# charlie_array_0805_v1.net
KiCad netlist of a schematic drawn in EAGLE
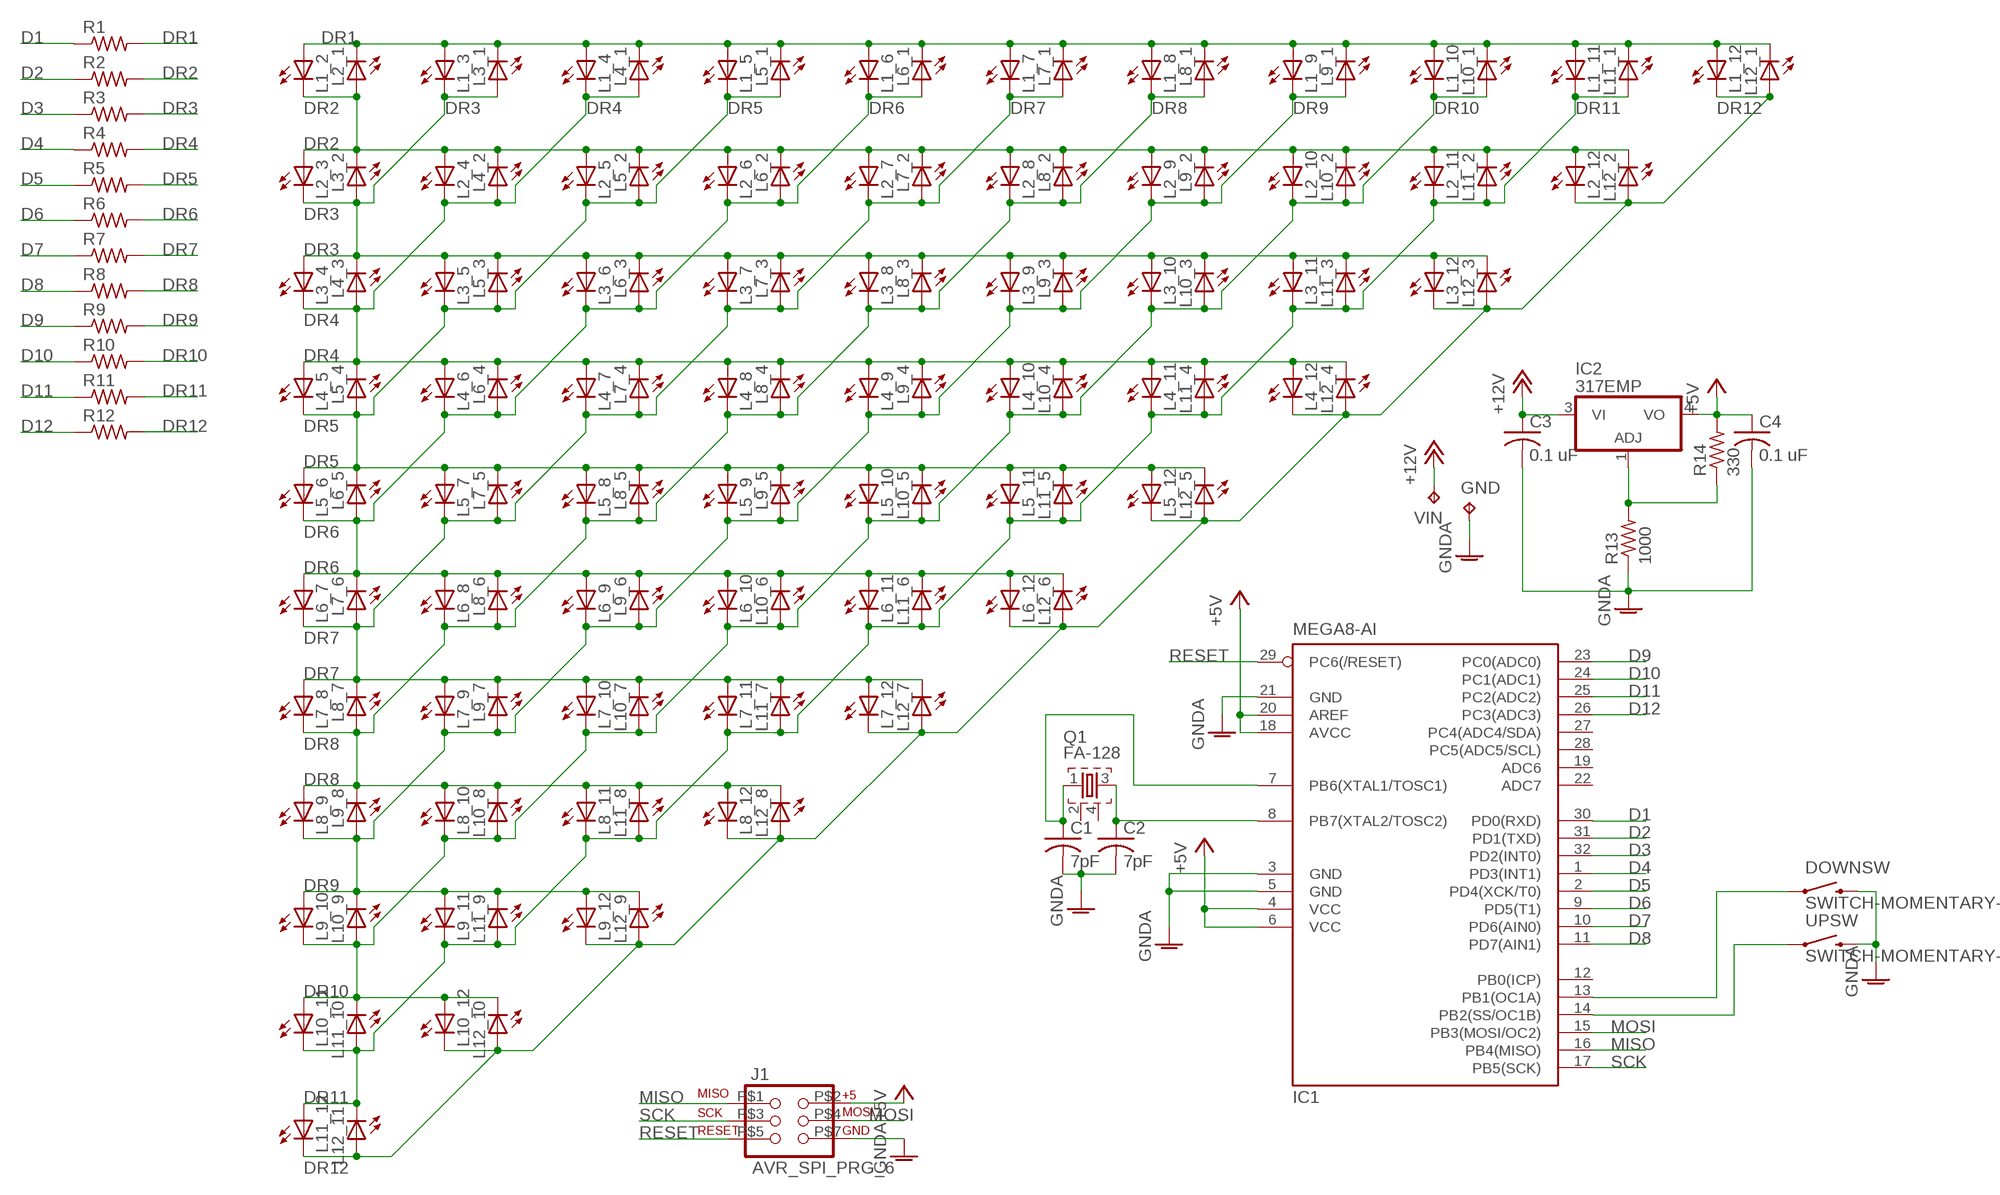
[diagram p0: schematic, sheet 1]

(export (version "E")
  (design (tool "Eeschema 10.0.6"))
  (components
    (comp (ref "C1")
      (value "7pF")
      (footprint "eagle-import:C0603")
      (libsource (lib "eagle-import") (part "C-USC0603"))
    )
    (comp (ref "C2")
      (value "7pF")
      (footprint "eagle-import:C0603")
      (libsource (lib "eagle-import") (part "C-USC0603"))
    )
    (comp (ref "C3")
      (value "0.1 uF")
      (footprint "eagle-import:C0603")
      (libsource (lib "eagle-import") (part "C-USC0603"))
    )
    (comp (ref "C4")
      (value "0.1 uF")
      (footprint "eagle-import:C0603")
      (libsource (lib "eagle-import") (part "C-USC0603"))
    )
    (comp (ref "DOWNSW")
      (value "SWITCH-MOMENTARY-2")
      (footprint "eagle-import:TACTILE_SWITCH_TALL")
      (libsource (lib "eagle-import") (part "SWITCH-MOMENTARY-2"))
    )
    (comp (ref "GND")
      (value "TPTP20SQ")
      (footprint "eagle-import:TP20SQ")
      (libsource (lib "eagle-import") (part "TPTP20SQ"))
    )
    (comp (ref "IC1")
      (value "MEGA8-AI")
      (footprint "eagle-import:TQFP32-08")
      (fields (field (name "MPN") "ATMEGA8-16AU"))
      (libsource (lib "eagle-import") (part "MEGA8-AI"))
    )
    (comp (ref "IC2")
      (value "317EMP")
      (footprint "eagle-import:SOT223")
      (libsource (lib "eagle-import") (part "317EMP"))
    )
    (comp (ref "J1")
      (value "AVR_SPI_PRG_6")
      (footprint "eagle-import:2X3_ICSP_SMD")
      (libsource (lib "eagle-import") (part "AVR_SPI_PRG_6"))
    )
    (comp (ref "L1_2")
      (value "LEDCHIPLED_0805")
      (footprint "eagle-import:CHIPLED_0805")
      (libsource (lib "eagle-import") (part "LEDCHIPLED_0805"))
    )
    (comp (ref "L1_3")
      (value "LEDCHIPLED_0805")
      (footprint "eagle-import:CHIPLED_0805")
      (libsource (lib "eagle-import") (part "LEDCHIPLED_0805"))
    )
    (comp (ref "L1_4")
      (value "LEDCHIPLED_0805")
      (footprint "eagle-import:CHIPLED_0805")
      (libsource (lib "eagle-import") (part "LEDCHIPLED_0805"))
    )
    (comp (ref "L1_5")
      (value "LEDCHIPLED_0805")
      (footprint "eagle-import:CHIPLED_0805")
      (libsource (lib "eagle-import") (part "LEDCHIPLED_0805"))
    )
    (comp (ref "L1_6")
      (value "LEDCHIPLED_0805")
      (footprint "eagle-import:CHIPLED_0805")
      (libsource (lib "eagle-import") (part "LEDCHIPLED_0805"))
    )
    (comp (ref "L1_7")
      (value "LEDCHIPLED_0805")
      (footprint "eagle-import:CHIPLED_0805")
      (libsource (lib "eagle-import") (part "LEDCHIPLED_0805"))
    )
    (comp (ref "L1_8")
      (value "LEDCHIPLED_0805")
      (footprint "eagle-import:CHIPLED_0805")
      (libsource (lib "eagle-import") (part "LEDCHIPLED_0805"))
    )
    (comp (ref "L1_9")
      (value "LEDCHIPLED_0805")
      (footprint "eagle-import:CHIPLED_0805")
      (libsource (lib "eagle-import") (part "LEDCHIPLED_0805"))
    )
    (comp (ref "L1_10")
      (value "LEDCHIPLED_0805")
      (footprint "eagle-import:CHIPLED_0805")
      (libsource (lib "eagle-import") (part "LEDCHIPLED_0805"))
    )
    (comp (ref "L1_11")
      (value "LEDCHIPLED_0805")
      (footprint "eagle-import:CHIPLED_0805")
      (libsource (lib "eagle-import") (part "LEDCHIPLED_0805"))
    )
    (comp (ref "L1_12")
      (value "LEDCHIPLED_0805")
      (footprint "eagle-import:CHIPLED_0805")
      (libsource (lib "eagle-import") (part "LEDCHIPLED_0805"))
    )
    (comp (ref "L2_1")
      (value "LEDCHIPLED_0805")
      (footprint "eagle-import:CHIPLED_0805")
      (libsource (lib "eagle-import") (part "LEDCHIPLED_0805"))
    )
    (comp (ref "L2_3")
      (value "LEDCHIPLED_0805")
      (footprint "eagle-import:CHIPLED_0805")
      (libsource (lib "eagle-import") (part "LEDCHIPLED_0805"))
    )
    (comp (ref "L2_4")
      (value "LEDCHIPLED_0805")
      (footprint "eagle-import:CHIPLED_0805")
      (libsource (lib "eagle-import") (part "LEDCHIPLED_0805"))
    )
    (comp (ref "L2_5")
      (value "LEDCHIPLED_0805")
      (footprint "eagle-import:CHIPLED_0805")
      (libsource (lib "eagle-import") (part "LEDCHIPLED_0805"))
    )
    (comp (ref "L2_6")
      (value "LEDCHIPLED_0805")
      (footprint "eagle-import:CHIPLED_0805")
      (libsource (lib "eagle-import") (part "LEDCHIPLED_0805"))
    )
    (comp (ref "L2_7")
      (value "LEDCHIPLED_0805")
      (footprint "eagle-import:CHIPLED_0805")
      (libsource (lib "eagle-import") (part "LEDCHIPLED_0805"))
    )
    (comp (ref "L2_8")
      (value "LEDCHIPLED_0805")
      (footprint "eagle-import:CHIPLED_0805")
      (libsource (lib "eagle-import") (part "LEDCHIPLED_0805"))
    )
    (comp (ref "L2_9")
      (value "LEDCHIPLED_0805")
      (footprint "eagle-import:CHIPLED_0805")
      (libsource (lib "eagle-import") (part "LEDCHIPLED_0805"))
    )
    (comp (ref "L2_10")
      (value "LEDCHIPLED_0805")
      (footprint "eagle-import:CHIPLED_0805")
      (libsource (lib "eagle-import") (part "LEDCHIPLED_0805"))
    )
    (comp (ref "L2_11")
      (value "LEDCHIPLED_0805")
      (footprint "eagle-import:CHIPLED_0805")
      (libsource (lib "eagle-import") (part "LEDCHIPLED_0805"))
    )
    (comp (ref "L2_12")
      (value "LEDCHIPLED_0805")
      (footprint "eagle-import:CHIPLED_0805")
      (libsource (lib "eagle-import") (part "LEDCHIPLED_0805"))
    )
    (comp (ref "L3_1")
      (value "LEDCHIPLED_0805")
      (footprint "eagle-import:CHIPLED_0805")
      (libsource (lib "eagle-import") (part "LEDCHIPLED_0805"))
    )
    (comp (ref "L3_2")
      (value "LEDCHIPLED_0805")
      (footprint "eagle-import:CHIPLED_0805")
      (libsource (lib "eagle-import") (part "LEDCHIPLED_0805"))
    )
    (comp (ref "L3_4")
      (value "LEDCHIPLED_0805")
      (footprint "eagle-import:CHIPLED_0805")
      (libsource (lib "eagle-import") (part "LEDCHIPLED_0805"))
    )
    (comp (ref "L3_5")
      (value "LEDCHIPLED_0805")
      (footprint "eagle-import:CHIPLED_0805")
      (libsource (lib "eagle-import") (part "LEDCHIPLED_0805"))
    )
    (comp (ref "L3_6")
      (value "LEDCHIPLED_0805")
      (footprint "eagle-import:CHIPLED_0805")
      (libsource (lib "eagle-import") (part "LEDCHIPLED_0805"))
    )
    (comp (ref "L3_7")
      (value "LEDCHIPLED_0805")
      (footprint "eagle-import:CHIPLED_0805")
      (libsource (lib "eagle-import") (part "LEDCHIPLED_0805"))
    )
    (comp (ref "L3_8")
      (value "LEDCHIPLED_0805")
      (footprint "eagle-import:CHIPLED_0805")
      (libsource (lib "eagle-import") (part "LEDCHIPLED_0805"))
    )
    (comp (ref "L3_9")
      (value "LEDCHIPLED_0805")
      (footprint "eagle-import:CHIPLED_0805")
      (libsource (lib "eagle-import") (part "LEDCHIPLED_0805"))
    )
    (comp (ref "L3_10")
      (value "LEDCHIPLED_0805")
      (footprint "eagle-import:CHIPLED_0805")
      (libsource (lib "eagle-import") (part "LEDCHIPLED_0805"))
    )
    (comp (ref "L3_11")
      (value "LEDCHIPLED_0805")
      (footprint "eagle-import:CHIPLED_0805")
      (libsource (lib "eagle-import") (part "LEDCHIPLED_0805"))
    )
    (comp (ref "L3_12")
      (value "LEDCHIPLED_0805")
      (footprint "eagle-import:CHIPLED_0805")
      (libsource (lib "eagle-import") (part "LEDCHIPLED_0805"))
    )
    (comp (ref "L4_1")
      (value "LEDCHIPLED_0805")
      (footprint "eagle-import:CHIPLED_0805")
      (libsource (lib "eagle-import") (part "LEDCHIPLED_0805"))
    )
    (comp (ref "L4_2")
      (value "LEDCHIPLED_0805")
      (footprint "eagle-import:CHIPLED_0805")
      (libsource (lib "eagle-import") (part "LEDCHIPLED_0805"))
    )
    (comp (ref "L4_3")
      (value "LEDCHIPLED_0805")
      (footprint "eagle-import:CHIPLED_0805")
      (libsource (lib "eagle-import") (part "LEDCHIPLED_0805"))
    )
    (comp (ref "L4_5")
      (value "LEDCHIPLED_0805")
      (footprint "eagle-import:CHIPLED_0805")
      (libsource (lib "eagle-import") (part "LEDCHIPLED_0805"))
    )
    (comp (ref "L4_6")
      (value "LEDCHIPLED_0805")
      (footprint "eagle-import:CHIPLED_0805")
      (libsource (lib "eagle-import") (part "LEDCHIPLED_0805"))
    )
    (comp (ref "L4_7")
      (value "LEDCHIPLED_0805")
      (footprint "eagle-import:CHIPLED_0805")
      (libsource (lib "eagle-import") (part "LEDCHIPLED_0805"))
    )
    (comp (ref "L4_8")
      (value "LEDCHIPLED_0805")
      (footprint "eagle-import:CHIPLED_0805")
      (libsource (lib "eagle-import") (part "LEDCHIPLED_0805"))
    )
    (comp (ref "L4_9")
      (value "LEDCHIPLED_0805")
      (footprint "eagle-import:CHIPLED_0805")
      (libsource (lib "eagle-import") (part "LEDCHIPLED_0805"))
    )
    (comp (ref "L4_10")
      (value "LEDCHIPLED_0805")
      (footprint "eagle-import:CHIPLED_0805")
      (libsource (lib "eagle-import") (part "LEDCHIPLED_0805"))
    )
    (comp (ref "L4_11")
      (value "LEDCHIPLED_0805")
      (footprint "eagle-import:CHIPLED_0805")
      (libsource (lib "eagle-import") (part "LEDCHIPLED_0805"))
    )
    (comp (ref "L4_12")
      (value "LEDCHIPLED_0805")
      (footprint "eagle-import:CHIPLED_0805")
      (libsource (lib "eagle-import") (part "LEDCHIPLED_0805"))
    )
    (comp (ref "L5_1")
      (value "LEDCHIPLED_0805")
      (footprint "eagle-import:CHIPLED_0805")
      (libsource (lib "eagle-import") (part "LEDCHIPLED_0805"))
    )
    (comp (ref "L5_2")
      (value "LEDCHIPLED_0805")
      (footprint "eagle-import:CHIPLED_0805")
      (libsource (lib "eagle-import") (part "LEDCHIPLED_0805"))
    )
    (comp (ref "L5_3")
      (value "LEDCHIPLED_0805")
      (footprint "eagle-import:CHIPLED_0805")
      (libsource (lib "eagle-import") (part "LEDCHIPLED_0805"))
    )
    (comp (ref "L5_4")
      (value "LEDCHIPLED_0805")
      (footprint "eagle-import:CHIPLED_0805")
      (libsource (lib "eagle-import") (part "LEDCHIPLED_0805"))
    )
    (comp (ref "L5_6")
      (value "LEDCHIPLED_0805")
      (footprint "eagle-import:CHIPLED_0805")
      (libsource (lib "eagle-import") (part "LEDCHIPLED_0805"))
    )
    (comp (ref "L5_7")
      (value "LEDCHIPLED_0805")
      (footprint "eagle-import:CHIPLED_0805")
      (libsource (lib "eagle-import") (part "LEDCHIPLED_0805"))
    )
    (comp (ref "L5_8")
      (value "LEDCHIPLED_0805")
      (footprint "eagle-import:CHIPLED_0805")
      (libsource (lib "eagle-import") (part "LEDCHIPLED_0805"))
    )
    (comp (ref "L5_9")
      (value "LEDCHIPLED_0805")
      (footprint "eagle-import:CHIPLED_0805")
      (libsource (lib "eagle-import") (part "LEDCHIPLED_0805"))
    )
    (comp (ref "L5_10")
      (value "LEDCHIPLED_0805")
      (footprint "eagle-import:CHIPLED_0805")
      (libsource (lib "eagle-import") (part "LEDCHIPLED_0805"))
    )
    (comp (ref "L5_11")
      (value "LEDCHIPLED_0805")
      (footprint "eagle-import:CHIPLED_0805")
      (libsource (lib "eagle-import") (part "LEDCHIPLED_0805"))
    )
    (comp (ref "L5_12")
      (value "LEDCHIPLED_0805")
      (footprint "eagle-import:CHIPLED_0805")
      (libsource (lib "eagle-import") (part "LEDCHIPLED_0805"))
    )
    (comp (ref "L6_1")
      (value "LEDCHIPLED_0805")
      (footprint "eagle-import:CHIPLED_0805")
      (libsource (lib "eagle-import") (part "LEDCHIPLED_0805"))
    )
    (comp (ref "L6_2")
      (value "LEDCHIPLED_0805")
      (footprint "eagle-import:CHIPLED_0805")
      (libsource (lib "eagle-import") (part "LEDCHIPLED_0805"))
    )
    (comp (ref "L6_3")
      (value "LEDCHIPLED_0805")
      (footprint "eagle-import:CHIPLED_0805")
      (libsource (lib "eagle-import") (part "LEDCHIPLED_0805"))
    )
    (comp (ref "L6_4")
      (value "LEDCHIPLED_0805")
      (footprint "eagle-import:CHIPLED_0805")
      (libsource (lib "eagle-import") (part "LEDCHIPLED_0805"))
    )
    (comp (ref "L6_5")
      (value "LEDCHIPLED_0805")
      (footprint "eagle-import:CHIPLED_0805")
      (libsource (lib "eagle-import") (part "LEDCHIPLED_0805"))
    )
    (comp (ref "L6_7")
      (value "LEDCHIPLED_0805")
      (footprint "eagle-import:CHIPLED_0805")
      (libsource (lib "eagle-import") (part "LEDCHIPLED_0805"))
    )
    (comp (ref "L6_8")
      (value "LEDCHIPLED_0805")
      (footprint "eagle-import:CHIPLED_0805")
      (libsource (lib "eagle-import") (part "LEDCHIPLED_0805"))
    )
    (comp (ref "L6_9")
      (value "LEDCHIPLED_0805")
      (footprint "eagle-import:CHIPLED_0805")
      (libsource (lib "eagle-import") (part "LEDCHIPLED_0805"))
    )
    (comp (ref "L6_10")
      (value "LEDCHIPLED_0805")
      (footprint "eagle-import:CHIPLED_0805")
      (libsource (lib "eagle-import") (part "LEDCHIPLED_0805"))
    )
    (comp (ref "L6_11")
      (value "LEDCHIPLED_0805")
      (footprint "eagle-import:CHIPLED_0805")
      (libsource (lib "eagle-import") (part "LEDCHIPLED_0805"))
    )
    (comp (ref "L6_12")
      (value "LEDCHIPLED_0805")
      (footprint "eagle-import:CHIPLED_0805")
      (libsource (lib "eagle-import") (part "LEDCHIPLED_0805"))
    )
    (comp (ref "L7_1")
      (value "LEDCHIPLED_0805")
      (footprint "eagle-import:CHIPLED_0805")
      (libsource (lib "eagle-import") (part "LEDCHIPLED_0805"))
    )
    (comp (ref "L7_2")
      (value "LEDCHIPLED_0805")
      (footprint "eagle-import:CHIPLED_0805")
      (libsource (lib "eagle-import") (part "LEDCHIPLED_0805"))
    )
    (comp (ref "L7_3")
      (value "LEDCHIPLED_0805")
      (footprint "eagle-import:CHIPLED_0805")
      (libsource (lib "eagle-import") (part "LEDCHIPLED_0805"))
    )
    (comp (ref "L7_4")
      (value "LEDCHIPLED_0805")
      (footprint "eagle-import:CHIPLED_0805")
      (libsource (lib "eagle-import") (part "LEDCHIPLED_0805"))
    )
    (comp (ref "L7_5")
      (value "LEDCHIPLED_0805")
      (footprint "eagle-import:CHIPLED_0805")
      (libsource (lib "eagle-import") (part "LEDCHIPLED_0805"))
    )
    (comp (ref "L7_6")
      (value "LEDCHIPLED_0805")
      (footprint "eagle-import:CHIPLED_0805")
      (libsource (lib "eagle-import") (part "LEDCHIPLED_0805"))
    )
    (comp (ref "L7_8")
      (value "LEDCHIPLED_0805")
      (footprint "eagle-import:CHIPLED_0805")
      (libsource (lib "eagle-import") (part "LEDCHIPLED_0805"))
    )
    (comp (ref "L7_9")
      (value "LEDCHIPLED_0805")
      (footprint "eagle-import:CHIPLED_0805")
      (libsource (lib "eagle-import") (part "LEDCHIPLED_0805"))
    )
    (comp (ref "L7_10")
      (value "LEDCHIPLED_0805")
      (footprint "eagle-import:CHIPLED_0805")
      (libsource (lib "eagle-import") (part "LEDCHIPLED_0805"))
    )
    (comp (ref "L7_11")
      (value "LEDCHIPLED_0805")
      (footprint "eagle-import:CHIPLED_0805")
      (libsource (lib "eagle-import") (part "LEDCHIPLED_0805"))
    )
    (comp (ref "L7_12")
      (value "LEDCHIPLED_0805")
      (footprint "eagle-import:CHIPLED_0805")
      (libsource (lib "eagle-import") (part "LEDCHIPLED_0805"))
    )
    (comp (ref "L8_1")
      (value "LEDCHIPLED_0805")
      (footprint "eagle-import:CHIPLED_0805")
      (libsource (lib "eagle-import") (part "LEDCHIPLED_0805"))
    )
    (comp (ref "L8_2")
      (value "LEDCHIPLED_0805")
      (footprint "eagle-import:CHIPLED_0805")
      (libsource (lib "eagle-import") (part "LEDCHIPLED_0805"))
    )
    (comp (ref "L8_3")
      (value "LEDCHIPLED_0805")
      (footprint "eagle-import:CHIPLED_0805")
      (libsource (lib "eagle-import") (part "LEDCHIPLED_0805"))
    )
    (comp (ref "L8_4")
      (value "LEDCHIPLED_0805")
      (footprint "eagle-import:CHIPLED_0805")
      (libsource (lib "eagle-import") (part "LEDCHIPLED_0805"))
    )
    (comp (ref "L8_5")
      (value "LEDCHIPLED_0805")
      (footprint "eagle-import:CHIPLED_0805")
      (libsource (lib "eagle-import") (part "LEDCHIPLED_0805"))
    )
    (comp (ref "L8_6")
      (value "LEDCHIPLED_0805")
      (footprint "eagle-import:CHIPLED_0805")
      (libsource (lib "eagle-import") (part "LEDCHIPLED_0805"))
    )
    (comp (ref "L8_7")
      (value "LEDCHIPLED_0805")
      (footprint "eagle-import:CHIPLED_0805")
      (libsource (lib "eagle-import") (part "LEDCHIPLED_0805"))
    )
    (comp (ref "L8_9")
      (value "LEDCHIPLED_0805")
      (footprint "eagle-import:CHIPLED_0805")
      (libsource (lib "eagle-import") (part "LEDCHIPLED_0805"))
    )
    (comp (ref "L8_10")
      (value "LEDCHIPLED_0805")
      (footprint "eagle-import:CHIPLED_0805")
      (libsource (lib "eagle-import") (part "LEDCHIPLED_0805"))
    )
    (comp (ref "L8_11")
      (value "LEDCHIPLED_0805")
      (footprint "eagle-import:CHIPLED_0805")
      (libsource (lib "eagle-import") (part "LEDCHIPLED_0805"))
    )
    (comp (ref "L8_12")
      (value "LEDCHIPLED_0805")
      (footprint "eagle-import:CHIPLED_0805")
      (libsource (lib "eagle-import") (part "LEDCHIPLED_0805"))
    )
    (comp (ref "L9_1")
      (value "LEDCHIPLED_0805")
      (footprint "eagle-import:CHIPLED_0805")
      (libsource (lib "eagle-import") (part "LEDCHIPLED_0805"))
    )
    (comp (ref "L9_2")
      (value "LEDCHIPLED_0805")
      (footprint "eagle-import:CHIPLED_0805")
      (libsource (lib "eagle-import") (part "LEDCHIPLED_0805"))
    )
    (comp (ref "L9_3")
      (value "LEDCHIPLED_0805")
      (footprint "eagle-import:CHIPLED_0805")
      (libsource (lib "eagle-import") (part "LEDCHIPLED_0805"))
    )
    (comp (ref "L9_4")
      (value "LEDCHIPLED_0805")
      (footprint "eagle-import:CHIPLED_0805")
      (libsource (lib "eagle-import") (part "LEDCHIPLED_0805"))
    )
    (comp (ref "L9_5")
      (value "LEDCHIPLED_0805")
      (footprint "eagle-import:CHIPLED_0805")
      (libsource (lib "eagle-import") (part "LEDCHIPLED_0805"))
    )
    (comp (ref "L9_6")
      (value "LEDCHIPLED_0805")
      (footprint "eagle-import:CHIPLED_0805")
      (libsource (lib "eagle-import") (part "LEDCHIPLED_0805"))
    )
    (comp (ref "L9_7")
      (value "LEDCHIPLED_0805")
      (footprint "eagle-import:CHIPLED_0805")
      (libsource (lib "eagle-import") (part "LEDCHIPLED_0805"))
    )
    (comp (ref "L9_8")
      (value "LEDCHIPLED_0805")
      (footprint "eagle-import:CHIPLED_0805")
      (libsource (lib "eagle-import") (part "LEDCHIPLED_0805"))
    )
    (comp (ref "L9_10")
      (value "LEDCHIPLED_0805")
      (footprint "eagle-import:CHIPLED_0805")
      (libsource (lib "eagle-import") (part "LEDCHIPLED_0805"))
    )
    (comp (ref "L9_11")
      (value "LEDCHIPLED_0805")
      (footprint "eagle-import:CHIPLED_0805")
      (libsource (lib "eagle-import") (part "LEDCHIPLED_0805"))
    )
    (comp (ref "L9_12")
      (value "LEDCHIPLED_0805")
      (footprint "eagle-import:CHIPLED_0805")
      (libsource (lib "eagle-import") (part "LEDCHIPLED_0805"))
    )
    (comp (ref "L10_1")
      (value "LEDCHIPLED_0805")
      (footprint "eagle-import:CHIPLED_0805")
      (libsource (lib "eagle-import") (part "LEDCHIPLED_0805"))
    )
    (comp (ref "L10_2")
      (value "LEDCHIPLED_0805")
      (footprint "eagle-import:CHIPLED_0805")
      (libsource (lib "eagle-import") (part "LEDCHIPLED_0805"))
    )
    (comp (ref "L10_3")
      (value "LEDCHIPLED_0805")
      (footprint "eagle-import:CHIPLED_0805")
      (libsource (lib "eagle-import") (part "LEDCHIPLED_0805"))
    )
    (comp (ref "L10_4")
      (value "LEDCHIPLED_0805")
      (footprint "eagle-import:CHIPLED_0805")
      (libsource (lib "eagle-import") (part "LEDCHIPLED_0805"))
    )
    (comp (ref "L10_5")
      (value "LEDCHIPLED_0805")
      (footprint "eagle-import:CHIPLED_0805")
      (libsource (lib "eagle-import") (part "LEDCHIPLED_0805"))
    )
    (comp (ref "L10_6")
      (value "LEDCHIPLED_0805")
      (footprint "eagle-import:CHIPLED_0805")
      (libsource (lib "eagle-import") (part "LEDCHIPLED_0805"))
    )
    (comp (ref "L10_7")
      (value "LEDCHIPLED_0805")
      (footprint "eagle-import:CHIPLED_0805")
      (libsource (lib "eagle-import") (part "LEDCHIPLED_0805"))
    )
    (comp (ref "L10_8")
      (value "LEDCHIPLED_0805")
      (footprint "eagle-import:CHIPLED_0805")
      (libsource (lib "eagle-import") (part "LEDCHIPLED_0805"))
    )
    (comp (ref "L10_9")
      (value "LEDCHIPLED_0805")
      (footprint "eagle-import:CHIPLED_0805")
      (libsource (lib "eagle-import") (part "LEDCHIPLED_0805"))
    )
    (comp (ref "L10_11")
      (value "LEDCHIPLED_0805")
      (footprint "eagle-import:CHIPLED_0805")
      (libsource (lib "eagle-import") (part "LEDCHIPLED_0805"))
    )
    (comp (ref "L10_12")
      (value "LEDCHIPLED_0805")
      (footprint "eagle-import:CHIPLED_0805")
      (libsource (lib "eagle-import") (part "LEDCHIPLED_0805"))
    )
    (comp (ref "L11_1")
      (value "LEDCHIPLED_0805")
      (footprint "eagle-import:CHIPLED_0805")
      (libsource (lib "eagle-import") (part "LEDCHIPLED_0805"))
    )
    (comp (ref "L11_2")
      (value "LEDCHIPLED_0805")
      (footprint "eagle-import:CHIPLED_0805")
      (libsource (lib "eagle-import") (part "LEDCHIPLED_0805"))
    )
    (comp (ref "L11_3")
      (value "LEDCHIPLED_0805")
      (footprint "eagle-import:CHIPLED_0805")
      (libsource (lib "eagle-import") (part "LEDCHIPLED_0805"))
    )
    (comp (ref "L11_4")
      (value "LEDCHIPLED_0805")
      (footprint "eagle-import:CHIPLED_0805")
      (libsource (lib "eagle-import") (part "LEDCHIPLED_0805"))
    )
    (comp (ref "L11_5")
      (value "LEDCHIPLED_0805")
      (footprint "eagle-import:CHIPLED_0805")
      (libsource (lib "eagle-import") (part "LEDCHIPLED_0805"))
    )
    (comp (ref "L11_6")
      (value "LEDCHIPLED_0805")
      (footprint "eagle-import:CHIPLED_0805")
      (libsource (lib "eagle-import") (part "LEDCHIPLED_0805"))
    )
    (comp (ref "L11_7")
      (value "LEDCHIPLED_0805")
      (footprint "eagle-import:CHIPLED_0805")
      (libsource (lib "eagle-import") (part "LEDCHIPLED_0805"))
    )
    (comp (ref "L11_8")
      (value "LEDCHIPLED_0805")
      (footprint "eagle-import:CHIPLED_0805")
      (libsource (lib "eagle-import") (part "LEDCHIPLED_0805"))
    )
    (comp (ref "L11_9")
      (value "LEDCHIPLED_0805")
      (footprint "eagle-import:CHIPLED_0805")
      (libsource (lib "eagle-import") (part "LEDCHIPLED_0805"))
    )
    (comp (ref "L11_10")
      (value "LEDCHIPLED_0805")
      (footprint "eagle-import:CHIPLED_0805")
      (libsource (lib "eagle-import") (part "LEDCHIPLED_0805"))
    )
    (comp (ref "L11_12")
      (value "LEDCHIPLED_0805")
      (footprint "eagle-import:CHIPLED_0805")
      (libsource (lib "eagle-import") (part "LEDCHIPLED_0805"))
    )
    (comp (ref "L12_1")
      (value "LEDCHIPLED_0805")
      (footprint "eagle-import:CHIPLED_0805")
      (libsource (lib "eagle-import") (part "LEDCHIPLED_0805"))
    )
    (comp (ref "L12_2")
      (value "LEDCHIPLED_0805")
      (footprint "eagle-import:CHIPLED_0805")
      (libsource (lib "eagle-import") (part "LEDCHIPLED_0805"))
    )
    (comp (ref "L12_3")
      (value "LEDCHIPLED_0805")
      (footprint "eagle-import:CHIPLED_0805")
      (libsource (lib "eagle-import") (part "LEDCHIPLED_0805"))
    )
    (comp (ref "L12_4")
      (value "LEDCHIPLED_0805")
      (footprint "eagle-import:CHIPLED_0805")
      (libsource (lib "eagle-import") (part "LEDCHIPLED_0805"))
    )
    (comp (ref "L12_5")
      (value "LEDCHIPLED_0805")
      (footprint "eagle-import:CHIPLED_0805")
      (libsource (lib "eagle-import") (part "LEDCHIPLED_0805"))
    )
    (comp (ref "L12_6")
      (value "LEDCHIPLED_0805")
      (footprint "eagle-import:CHIPLED_0805")
      (libsource (lib "eagle-import") (part "LEDCHIPLED_0805"))
    )
    (comp (ref "L12_7")
      (value "LEDCHIPLED_0805")
      (footprint "eagle-import:CHIPLED_0805")
      (libsource (lib "eagle-import") (part "LEDCHIPLED_0805"))
    )
    (comp (ref "L12_8")
      (value "LEDCHIPLED_0805")
      (footprint "eagle-import:CHIPLED_0805")
      (libsource (lib "eagle-import") (part "LEDCHIPLED_0805"))
    )
    (comp (ref "L12_9")
      (value "LEDCHIPLED_0805")
      (footprint "eagle-import:CHIPLED_0805")
      (libsource (lib "eagle-import") (part "LEDCHIPLED_0805"))
    )
    (comp (ref "L12_10")
      (value "LEDCHIPLED_0805")
      (footprint "eagle-import:CHIPLED_0805")
      (libsource (lib "eagle-import") (part "LEDCHIPLED_0805"))
    )
    (comp (ref "L12_11")
      (value "LEDCHIPLED_0805")
      (footprint "eagle-import:CHIPLED_0805")
      (libsource (lib "eagle-import") (part "LEDCHIPLED_0805"))
    )
    (comp (ref "Q1")
      (value "FA-128")
      (footprint "eagle-import:FA-128")
      (libsource (lib "eagle-import") (part "FA-128"))
    )
    (comp (ref "R1")
      (value "R-US_R0603")
      (footprint "eagle-import:R0603")
      (libsource (lib "eagle-import") (part "R-US_R0603"))
    )
    (comp (ref "R2")
      (value "R-US_R0603")
      (footprint "eagle-import:R0603")
      (libsource (lib "eagle-import") (part "R-US_R0603"))
    )
    (comp (ref "R3")
      (value "R-US_R0603")
      (footprint "eagle-import:R0603")
      (libsource (lib "eagle-import") (part "R-US_R0603"))
    )
    (comp (ref "R4")
      (value "R-US_R0603")
      (footprint "eagle-import:R0603")
      (libsource (lib "eagle-import") (part "R-US_R0603"))
    )
    (comp (ref "R5")
      (value "R-US_R0603")
      (footprint "eagle-import:R0603")
      (libsource (lib "eagle-import") (part "R-US_R0603"))
    )
    (comp (ref "R6")
      (value "R-US_R0603")
      (footprint "eagle-import:R0603")
      (libsource (lib "eagle-import") (part "R-US_R0603"))
    )
    (comp (ref "R7")
      (value "R-US_R0603")
      (footprint "eagle-import:R0603")
      (libsource (lib "eagle-import") (part "R-US_R0603"))
    )
    (comp (ref "R8")
      (value "R-US_R0603")
      (footprint "eagle-import:R0603")
      (libsource (lib "eagle-import") (part "R-US_R0603"))
    )
    (comp (ref "R9")
      (value "R-US_R0603")
      (footprint "eagle-import:R0603")
      (libsource (lib "eagle-import") (part "R-US_R0603"))
    )
    (comp (ref "R10")
      (value "R-US_R0603")
      (footprint "eagle-import:R0603")
      (libsource (lib "eagle-import") (part "R-US_R0603"))
    )
    (comp (ref "R11")
      (value "R-US_R0603")
      (footprint "eagle-import:R0603")
      (libsource (lib "eagle-import") (part "R-US_R0603"))
    )
    (comp (ref "R12")
      (value "R-US_R0603")
      (footprint "eagle-import:R0603")
      (libsource (lib "eagle-import") (part "R-US_R0603"))
    )
    (comp (ref "R13")
      (value "1000")
      (footprint "eagle-import:R0603")
      (libsource (lib "eagle-import") (part "R-US_R0603"))
    )
    (comp (ref "R14")
      (value "330")
      (footprint "eagle-import:R0603")
      (libsource (lib "eagle-import") (part "R-US_R0603"))
    )
    (comp (ref "UPSW")
      (value "SWITCH-MOMENTARY-2")
      (footprint "eagle-import:TACTILE_SWITCH_TALL")
      (libsource (lib "eagle-import") (part "SWITCH-MOMENTARY-2"))
    )
    (comp (ref "VIN")
      (value "TPTP20SQ")
      (footprint "eagle-import:TP20SQ")
      (libsource (lib "eagle-import") (part "TPTP20SQ"))
    )
  )
  (nets
    (net (code "1") (name "+5V") (class "Default")
      (node (ref "C4") (pin "1") (pinfunction "1_1") (pintype "passive"))
      (node (ref "IC1") (pin "18") (pinfunction "AVCC_18") (pintype "power_in"))
      (node (ref "IC1") (pin "20") (pinfunction "AREF_20") (pintype "passive"))
      (node (ref "IC1") (pin "4") (pinfunction "VCC_4") (pintype "power_in"))
      (node (ref "IC1") (pin "6") (pinfunction "VCC_6") (pintype "power_in"))
      (node (ref "IC2") (pin "4") (pinfunction "VO_4") (pintype "passive"))
      (node (ref "J1") (pin "P$2") (pinfunction "2_P$2") (pintype "passive"))
      (node (ref "R14") (pin "2") (pinfunction "2_2") (pintype "passive"))
    )
    (net (code "2") (name "+12V") (class "Default")
      (node (ref "C3") (pin "1") (pinfunction "1_1") (pintype "passive"))
      (node (ref "IC2") (pin "3") (pinfunction "VI_3") (pintype "input"))
      (node (ref "VIN") (pin "TP") (pinfunction "TP_TP") (pintype "input"))
    )
    (net (code "3") (name "/D1") (class "Default")
      (node (ref "IC1") (pin "30") (pinfunction "PD0(RXD)_30") (pintype "bidirectional"))
      (node (ref "R1") (pin "1") (pinfunction "1_1") (pintype "passive"))
    )
    (net (code "4") (name "/D2") (class "Default")
      (node (ref "IC1") (pin "31") (pinfunction "PD1(TXD)_31") (pintype "bidirectional"))
      (node (ref "R2") (pin "1") (pinfunction "1_1") (pintype "passive"))
    )
    (net (code "5") (name "/D3") (class "Default")
      (node (ref "IC1") (pin "32") (pinfunction "PD2(INT0)_32") (pintype "bidirectional"))
      (node (ref "R3") (pin "1") (pinfunction "1_1") (pintype "passive"))
    )
    (net (code "6") (name "/D4") (class "Default")
      (node (ref "IC1") (pin "1") (pinfunction "PD3(INT1)_1") (pintype "bidirectional"))
      (node (ref "R4") (pin "1") (pinfunction "1_1") (pintype "passive"))
    )
    (net (code "7") (name "/D5") (class "Default")
      (node (ref "IC1") (pin "2") (pinfunction "PD4(XCK/T0)_2") (pintype "bidirectional"))
      (node (ref "R5") (pin "1") (pinfunction "1_1") (pintype "passive"))
    )
    (net (code "8") (name "/D6") (class "Default")
      (node (ref "IC1") (pin "9") (pinfunction "PD5(T1)_9") (pintype "bidirectional"))
      (node (ref "R6") (pin "1") (pinfunction "1_1") (pintype "passive"))
    )
    (net (code "9") (name "/D7") (class "Default")
      (node (ref "IC1") (pin "10") (pinfunction "PD6(AIN0)_10") (pintype "bidirectional"))
      (node (ref "R7") (pin "1") (pinfunction "1_1") (pintype "passive"))
    )
    (net (code "10") (name "/D8") (class "Default")
      (node (ref "IC1") (pin "11") (pinfunction "PD7(AIN1)_11") (pintype "bidirectional"))
      (node (ref "R8") (pin "1") (pinfunction "1_1") (pintype "passive"))
    )
    (net (code "11") (name "/D9") (class "Default")
      (node (ref "IC1") (pin "23") (pinfunction "PC0(ADC0)_23") (pintype "bidirectional"))
      (node (ref "R9") (pin "1") (pinfunction "1_1") (pintype "passive"))
    )
    (net (code "12") (name "/D10") (class "Default")
      (node (ref "IC1") (pin "24") (pinfunction "PC1(ADC1)_24") (pintype "bidirectional"))
      (node (ref "R10") (pin "1") (pinfunction "1_1") (pintype "passive"))
    )
    (net (code "13") (name "/D11") (class "Default")
      (node (ref "IC1") (pin "25") (pinfunction "PC2(ADC2)_25") (pintype "bidirectional"))
      (node (ref "R11") (pin "1") (pinfunction "1_1") (pintype "passive"))
    )
    (net (code "14") (name "/D12") (class "Default")
      (node (ref "IC1") (pin "26") (pinfunction "PC3(ADC3)_26") (pintype "bidirectional"))
      (node (ref "R12") (pin "1") (pinfunction "1_1") (pintype "passive"))
    )
    (net (code "15") (name "/DR1") (class "Default")
      (node (ref "L10_1") (pin "C") (pinfunction "C_C") (pintype "passive"))
      (node (ref "L11_1") (pin "C") (pinfunction "C_C") (pintype "passive"))
      (node (ref "L12_1") (pin "C") (pinfunction "C_C") (pintype "passive"))
      (node (ref "L1_10") (pin "A") (pinfunction "A_A") (pintype "passive"))
      (node (ref "L1_11") (pin "A") (pinfunction "A_A") (pintype "passive"))
      (node (ref "L1_12") (pin "A") (pinfunction "A_A") (pintype "passive"))
      (node (ref "L1_2") (pin "A") (pinfunction "A_A") (pintype "passive"))
      (node (ref "L1_3") (pin "A") (pinfunction "A_A") (pintype "passive"))
      (node (ref "L1_4") (pin "A") (pinfunction "A_A") (pintype "passive"))
      (node (ref "L1_5") (pin "A") (pinfunction "A_A") (pintype "passive"))
      (node (ref "L1_6") (pin "A") (pinfunction "A_A") (pintype "passive"))
      (node (ref "L1_7") (pin "A") (pinfunction "A_A") (pintype "passive"))
      (node (ref "L1_8") (pin "A") (pinfunction "A_A") (pintype "passive"))
      (node (ref "L1_9") (pin "A") (pinfunction "A_A") (pintype "passive"))
      (node (ref "L2_1") (pin "C") (pinfunction "C_C") (pintype "passive"))
      (node (ref "L3_1") (pin "C") (pinfunction "C_C") (pintype "passive"))
      (node (ref "L4_1") (pin "C") (pinfunction "C_C") (pintype "passive"))
      (node (ref "L5_1") (pin "C") (pinfunction "C_C") (pintype "passive"))
      (node (ref "L6_1") (pin "C") (pinfunction "C_C") (pintype "passive"))
      (node (ref "L7_1") (pin "C") (pinfunction "C_C") (pintype "passive"))
      (node (ref "L8_1") (pin "C") (pinfunction "C_C") (pintype "passive"))
      (node (ref "L9_1") (pin "C") (pinfunction "C_C") (pintype "passive"))
      (node (ref "R1") (pin "2") (pinfunction "2_2") (pintype "passive"))
    )
    (net (code "16") (name "/DR2") (class "Default")
      (node (ref "L10_2") (pin "C") (pinfunction "C_C") (pintype "passive"))
      (node (ref "L11_2") (pin "C") (pinfunction "C_C") (pintype "passive"))
      (node (ref "L12_2") (pin "C") (pinfunction "C_C") (pintype "passive"))
      (node (ref "L1_2") (pin "C") (pinfunction "C_C") (pintype "passive"))
      (node (ref "L2_1") (pin "A") (pinfunction "A_A") (pintype "passive"))
      (node (ref "L2_10") (pin "A") (pinfunction "A_A") (pintype "passive"))
      (node (ref "L2_11") (pin "A") (pinfunction "A_A") (pintype "passive"))
      (node (ref "L2_12") (pin "A") (pinfunction "A_A") (pintype "passive"))
      (node (ref "L2_3") (pin "A") (pinfunction "A_A") (pintype "passive"))
      (node (ref "L2_4") (pin "A") (pinfunction "A_A") (pintype "passive"))
      (node (ref "L2_5") (pin "A") (pinfunction "A_A") (pintype "passive"))
      (node (ref "L2_6") (pin "A") (pinfunction "A_A") (pintype "passive"))
      (node (ref "L2_7") (pin "A") (pinfunction "A_A") (pintype "passive"))
      (node (ref "L2_8") (pin "A") (pinfunction "A_A") (pintype "passive"))
      (node (ref "L2_9") (pin "A") (pinfunction "A_A") (pintype "passive"))
      (node (ref "L3_2") (pin "C") (pinfunction "C_C") (pintype "passive"))
      (node (ref "L4_2") (pin "C") (pinfunction "C_C") (pintype "passive"))
      (node (ref "L5_2") (pin "C") (pinfunction "C_C") (pintype "passive"))
      (node (ref "L6_2") (pin "C") (pinfunction "C_C") (pintype "passive"))
      (node (ref "L7_2") (pin "C") (pinfunction "C_C") (pintype "passive"))
      (node (ref "L8_2") (pin "C") (pinfunction "C_C") (pintype "passive"))
      (node (ref "L9_2") (pin "C") (pinfunction "C_C") (pintype "passive"))
      (node (ref "R2") (pin "2") (pinfunction "2_2") (pintype "passive"))
    )
    (net (code "17") (name "/DR3") (class "Default")
      (node (ref "L10_3") (pin "C") (pinfunction "C_C") (pintype "passive"))
      (node (ref "L11_3") (pin "C") (pinfunction "C_C") (pintype "passive"))
      (node (ref "L12_3") (pin "C") (pinfunction "C_C") (pintype "passive"))
      (node (ref "L1_3") (pin "C") (pinfunction "C_C") (pintype "passive"))
      (node (ref "L2_3") (pin "C") (pinfunction "C_C") (pintype "passive"))
      (node (ref "L3_1") (pin "A") (pinfunction "A_A") (pintype "passive"))
      (node (ref "L3_10") (pin "A") (pinfunction "A_A") (pintype "passive"))
      (node (ref "L3_11") (pin "A") (pinfunction "A_A") (pintype "passive"))
      (node (ref "L3_12") (pin "A") (pinfunction "A_A") (pintype "passive"))
      (node (ref "L3_2") (pin "A") (pinfunction "A_A") (pintype "passive"))
      (node (ref "L3_4") (pin "A") (pinfunction "A_A") (pintype "passive"))
      (node (ref "L3_5") (pin "A") (pinfunction "A_A") (pintype "passive"))
      (node (ref "L3_6") (pin "A") (pinfunction "A_A") (pintype "passive"))
      (node (ref "L3_7") (pin "A") (pinfunction "A_A") (pintype "passive"))
      (node (ref "L3_8") (pin "A") (pinfunction "A_A") (pintype "passive"))
      (node (ref "L3_9") (pin "A") (pinfunction "A_A") (pintype "passive"))
      (node (ref "L4_3") (pin "C") (pinfunction "C_C") (pintype "passive"))
      (node (ref "L5_3") (pin "C") (pinfunction "C_C") (pintype "passive"))
      (node (ref "L6_3") (pin "C") (pinfunction "C_C") (pintype "passive"))
      (node (ref "L7_3") (pin "C") (pinfunction "C_C") (pintype "passive"))
      (node (ref "L8_3") (pin "C") (pinfunction "C_C") (pintype "passive"))
      (node (ref "L9_3") (pin "C") (pinfunction "C_C") (pintype "passive"))
      (node (ref "R3") (pin "2") (pinfunction "2_2") (pintype "passive"))
    )
    (net (code "18") (name "/DR4") (class "Default")
      (node (ref "L10_4") (pin "C") (pinfunction "C_C") (pintype "passive"))
      (node (ref "L11_4") (pin "C") (pinfunction "C_C") (pintype "passive"))
      (node (ref "L12_4") (pin "C") (pinfunction "C_C") (pintype "passive"))
      (node (ref "L1_4") (pin "C") (pinfunction "C_C") (pintype "passive"))
      (node (ref "L2_4") (pin "C") (pinfunction "C_C") (pintype "passive"))
      (node (ref "L3_4") (pin "C") (pinfunction "C_C") (pintype "passive"))
      (node (ref "L4_1") (pin "A") (pinfunction "A_A") (pintype "passive"))
      (node (ref "L4_10") (pin "A") (pinfunction "A_A") (pintype "passive"))
      (node (ref "L4_11") (pin "A") (pinfunction "A_A") (pintype "passive"))
      (node (ref "L4_12") (pin "A") (pinfunction "A_A") (pintype "passive"))
      (node (ref "L4_2") (pin "A") (pinfunction "A_A") (pintype "passive"))
      (node (ref "L4_3") (pin "A") (pinfunction "A_A") (pintype "passive"))
      (node (ref "L4_5") (pin "A") (pinfunction "A_A") (pintype "passive"))
      (node (ref "L4_6") (pin "A") (pinfunction "A_A") (pintype "passive"))
      (node (ref "L4_7") (pin "A") (pinfunction "A_A") (pintype "passive"))
      (node (ref "L4_8") (pin "A") (pinfunction "A_A") (pintype "passive"))
      (node (ref "L4_9") (pin "A") (pinfunction "A_A") (pintype "passive"))
      (node (ref "L5_4") (pin "C") (pinfunction "C_C") (pintype "passive"))
      (node (ref "L6_4") (pin "C") (pinfunction "C_C") (pintype "passive"))
      (node (ref "L7_4") (pin "C") (pinfunction "C_C") (pintype "passive"))
      (node (ref "L8_4") (pin "C") (pinfunction "C_C") (pintype "passive"))
      (node (ref "L9_4") (pin "C") (pinfunction "C_C") (pintype "passive"))
      (node (ref "R4") (pin "2") (pinfunction "2_2") (pintype "passive"))
    )
    (net (code "19") (name "/DR5") (class "Default")
      (node (ref "L10_5") (pin "C") (pinfunction "C_C") (pintype "passive"))
      (node (ref "L11_5") (pin "C") (pinfunction "C_C") (pintype "passive"))
      (node (ref "L12_5") (pin "C") (pinfunction "C_C") (pintype "passive"))
      (node (ref "L1_5") (pin "C") (pinfunction "C_C") (pintype "passive"))
      (node (ref "L2_5") (pin "C") (pinfunction "C_C") (pintype "passive"))
      (node (ref "L3_5") (pin "C") (pinfunction "C_C") (pintype "passive"))
      (node (ref "L4_5") (pin "C") (pinfunction "C_C") (pintype "passive"))
      (node (ref "L5_1") (pin "A") (pinfunction "A_A") (pintype "passive"))
      (node (ref "L5_10") (pin "A") (pinfunction "A_A") (pintype "passive"))
      (node (ref "L5_11") (pin "A") (pinfunction "A_A") (pintype "passive"))
      (node (ref "L5_12") (pin "A") (pinfunction "A_A") (pintype "passive"))
      (node (ref "L5_2") (pin "A") (pinfunction "A_A") (pintype "passive"))
      (node (ref "L5_3") (pin "A") (pinfunction "A_A") (pintype "passive"))
      (node (ref "L5_4") (pin "A") (pinfunction "A_A") (pintype "passive"))
      (node (ref "L5_6") (pin "A") (pinfunction "A_A") (pintype "passive"))
      (node (ref "L5_7") (pin "A") (pinfunction "A_A") (pintype "passive"))
      (node (ref "L5_8") (pin "A") (pinfunction "A_A") (pintype "passive"))
      (node (ref "L5_9") (pin "A") (pinfunction "A_A") (pintype "passive"))
      (node (ref "L6_5") (pin "C") (pinfunction "C_C") (pintype "passive"))
      (node (ref "L7_5") (pin "C") (pinfunction "C_C") (pintype "passive"))
      (node (ref "L8_5") (pin "C") (pinfunction "C_C") (pintype "passive"))
      (node (ref "L9_5") (pin "C") (pinfunction "C_C") (pintype "passive"))
      (node (ref "R5") (pin "2") (pinfunction "2_2") (pintype "passive"))
    )
    (net (code "20") (name "/DR6") (class "Default")
      (node (ref "L10_6") (pin "C") (pinfunction "C_C") (pintype "passive"))
      (node (ref "L11_6") (pin "C") (pinfunction "C_C") (pintype "passive"))
      (node (ref "L12_6") (pin "C") (pinfunction "C_C") (pintype "passive"))
      (node (ref "L1_6") (pin "C") (pinfunction "C_C") (pintype "passive"))
      (node (ref "L2_6") (pin "C") (pinfunction "C_C") (pintype "passive"))
      (node (ref "L3_6") (pin "C") (pinfunction "C_C") (pintype "passive"))
      (node (ref "L4_6") (pin "C") (pinfunction "C_C") (pintype "passive"))
      (node (ref "L5_6") (pin "C") (pinfunction "C_C") (pintype "passive"))
      (node (ref "L6_1") (pin "A") (pinfunction "A_A") (pintype "passive"))
      (node (ref "L6_10") (pin "A") (pinfunction "A_A") (pintype "passive"))
      (node (ref "L6_11") (pin "A") (pinfunction "A_A") (pintype "passive"))
      (node (ref "L6_12") (pin "A") (pinfunction "A_A") (pintype "passive"))
      (node (ref "L6_2") (pin "A") (pinfunction "A_A") (pintype "passive"))
      (node (ref "L6_3") (pin "A") (pinfunction "A_A") (pintype "passive"))
      (node (ref "L6_4") (pin "A") (pinfunction "A_A") (pintype "passive"))
      (node (ref "L6_5") (pin "A") (pinfunction "A_A") (pintype "passive"))
      (node (ref "L6_7") (pin "A") (pinfunction "A_A") (pintype "passive"))
      (node (ref "L6_8") (pin "A") (pinfunction "A_A") (pintype "passive"))
      (node (ref "L6_9") (pin "A") (pinfunction "A_A") (pintype "passive"))
      (node (ref "L7_6") (pin "C") (pinfunction "C_C") (pintype "passive"))
      (node (ref "L8_6") (pin "C") (pinfunction "C_C") (pintype "passive"))
      (node (ref "L9_6") (pin "C") (pinfunction "C_C") (pintype "passive"))
      (node (ref "R6") (pin "2") (pinfunction "2_2") (pintype "passive"))
    )
    (net (code "21") (name "/DR7") (class "Default")
      (node (ref "L10_7") (pin "C") (pinfunction "C_C") (pintype "passive"))
      (node (ref "L11_7") (pin "C") (pinfunction "C_C") (pintype "passive"))
      (node (ref "L12_7") (pin "C") (pinfunction "C_C") (pintype "passive"))
      (node (ref "L1_7") (pin "C") (pinfunction "C_C") (pintype "passive"))
      (node (ref "L2_7") (pin "C") (pinfunction "C_C") (pintype "passive"))
      (node (ref "L3_7") (pin "C") (pinfunction "C_C") (pintype "passive"))
      (node (ref "L4_7") (pin "C") (pinfunction "C_C") (pintype "passive"))
      (node (ref "L5_7") (pin "C") (pinfunction "C_C") (pintype "passive"))
      (node (ref "L6_7") (pin "C") (pinfunction "C_C") (pintype "passive"))
      (node (ref "L7_1") (pin "A") (pinfunction "A_A") (pintype "passive"))
      (node (ref "L7_10") (pin "A") (pinfunction "A_A") (pintype "passive"))
      (node (ref "L7_11") (pin "A") (pinfunction "A_A") (pintype "passive"))
      (node (ref "L7_12") (pin "A") (pinfunction "A_A") (pintype "passive"))
      (node (ref "L7_2") (pin "A") (pinfunction "A_A") (pintype "passive"))
      (node (ref "L7_3") (pin "A") (pinfunction "A_A") (pintype "passive"))
      (node (ref "L7_4") (pin "A") (pinfunction "A_A") (pintype "passive"))
      (node (ref "L7_5") (pin "A") (pinfunction "A_A") (pintype "passive"))
      (node (ref "L7_6") (pin "A") (pinfunction "A_A") (pintype "passive"))
      (node (ref "L7_8") (pin "A") (pinfunction "A_A") (pintype "passive"))
      (node (ref "L7_9") (pin "A") (pinfunction "A_A") (pintype "passive"))
      (node (ref "L8_7") (pin "C") (pinfunction "C_C") (pintype "passive"))
      (node (ref "L9_7") (pin "C") (pinfunction "C_C") (pintype "passive"))
      (node (ref "R7") (pin "2") (pinfunction "2_2") (pintype "passive"))
    )
    (net (code "22") (name "/DR8") (class "Default")
      (node (ref "L10_8") (pin "C") (pinfunction "C_C") (pintype "passive"))
      (node (ref "L11_8") (pin "C") (pinfunction "C_C") (pintype "passive"))
      (node (ref "L12_8") (pin "C") (pinfunction "C_C") (pintype "passive"))
      (node (ref "L1_8") (pin "C") (pinfunction "C_C") (pintype "passive"))
      (node (ref "L2_8") (pin "C") (pinfunction "C_C") (pintype "passive"))
      (node (ref "L3_8") (pin "C") (pinfunction "C_C") (pintype "passive"))
      (node (ref "L4_8") (pin "C") (pinfunction "C_C") (pintype "passive"))
      (node (ref "L5_8") (pin "C") (pinfunction "C_C") (pintype "passive"))
      (node (ref "L6_8") (pin "C") (pinfunction "C_C") (pintype "passive"))
      (node (ref "L7_8") (pin "C") (pinfunction "C_C") (pintype "passive"))
      (node (ref "L8_1") (pin "A") (pinfunction "A_A") (pintype "passive"))
      (node (ref "L8_10") (pin "A") (pinfunction "A_A") (pintype "passive"))
      (node (ref "L8_11") (pin "A") (pinfunction "A_A") (pintype "passive"))
      (node (ref "L8_12") (pin "A") (pinfunction "A_A") (pintype "passive"))
      (node (ref "L8_2") (pin "A") (pinfunction "A_A") (pintype "passive"))
      (node (ref "L8_3") (pin "A") (pinfunction "A_A") (pintype "passive"))
      (node (ref "L8_4") (pin "A") (pinfunction "A_A") (pintype "passive"))
      (node (ref "L8_5") (pin "A") (pinfunction "A_A") (pintype "passive"))
      (node (ref "L8_6") (pin "A") (pinfunction "A_A") (pintype "passive"))
      (node (ref "L8_7") (pin "A") (pinfunction "A_A") (pintype "passive"))
      (node (ref "L8_9") (pin "A") (pinfunction "A_A") (pintype "passive"))
      (node (ref "L9_8") (pin "C") (pinfunction "C_C") (pintype "passive"))
      (node (ref "R8") (pin "2") (pinfunction "2_2") (pintype "passive"))
    )
    (net (code "23") (name "/DR9") (class "Default")
      (node (ref "L10_9") (pin "C") (pinfunction "C_C") (pintype "passive"))
      (node (ref "L11_9") (pin "C") (pinfunction "C_C") (pintype "passive"))
      (node (ref "L12_9") (pin "C") (pinfunction "C_C") (pintype "passive"))
      (node (ref "L1_9") (pin "C") (pinfunction "C_C") (pintype "passive"))
      (node (ref "L2_9") (pin "C") (pinfunction "C_C") (pintype "passive"))
      (node (ref "L3_9") (pin "C") (pinfunction "C_C") (pintype "passive"))
      (node (ref "L4_9") (pin "C") (pinfunction "C_C") (pintype "passive"))
      (node (ref "L5_9") (pin "C") (pinfunction "C_C") (pintype "passive"))
      (node (ref "L6_9") (pin "C") (pinfunction "C_C") (pintype "passive"))
      (node (ref "L7_9") (pin "C") (pinfunction "C_C") (pintype "passive"))
      (node (ref "L8_9") (pin "C") (pinfunction "C_C") (pintype "passive"))
      (node (ref "L9_1") (pin "A") (pinfunction "A_A") (pintype "passive"))
      (node (ref "L9_10") (pin "A") (pinfunction "A_A") (pintype "passive"))
      (node (ref "L9_11") (pin "A") (pinfunction "A_A") (pintype "passive"))
      (node (ref "L9_12") (pin "A") (pinfunction "A_A") (pintype "passive"))
      (node (ref "L9_2") (pin "A") (pinfunction "A_A") (pintype "passive"))
      (node (ref "L9_3") (pin "A") (pinfunction "A_A") (pintype "passive"))
      (node (ref "L9_4") (pin "A") (pinfunction "A_A") (pintype "passive"))
      (node (ref "L9_5") (pin "A") (pinfunction "A_A") (pintype "passive"))
      (node (ref "L9_6") (pin "A") (pinfunction "A_A") (pintype "passive"))
      (node (ref "L9_7") (pin "A") (pinfunction "A_A") (pintype "passive"))
      (node (ref "L9_8") (pin "A") (pinfunction "A_A") (pintype "passive"))
      (node (ref "R9") (pin "2") (pinfunction "2_2") (pintype "passive"))
    )
    (net (code "24") (name "/DR10") (class "Default")
      (node (ref "L10_1") (pin "A") (pinfunction "A_A") (pintype "passive"))
      (node (ref "L10_11") (pin "A") (pinfunction "A_A") (pintype "passive"))
      (node (ref "L10_12") (pin "A") (pinfunction "A_A") (pintype "passive"))
      (node (ref "L10_2") (pin "A") (pinfunction "A_A") (pintype "passive"))
      (node (ref "L10_3") (pin "A") (pinfunction "A_A") (pintype "passive"))
      (node (ref "L10_4") (pin "A") (pinfunction "A_A") (pintype "passive"))
      (node (ref "L10_5") (pin "A") (pinfunction "A_A") (pintype "passive"))
      (node (ref "L10_6") (pin "A") (pinfunction "A_A") (pintype "passive"))
      (node (ref "L10_7") (pin "A") (pinfunction "A_A") (pintype "passive"))
      (node (ref "L10_8") (pin "A") (pinfunction "A_A") (pintype "passive"))
      (node (ref "L10_9") (pin "A") (pinfunction "A_A") (pintype "passive"))
      (node (ref "L11_10") (pin "C") (pinfunction "C_C") (pintype "passive"))
      (node (ref "L12_10") (pin "C") (pinfunction "C_C") (pintype "passive"))
      (node (ref "L1_10") (pin "C") (pinfunction "C_C") (pintype "passive"))
      (node (ref "L2_10") (pin "C") (pinfunction "C_C") (pintype "passive"))
      (node (ref "L3_10") (pin "C") (pinfunction "C_C") (pintype "passive"))
      (node (ref "L4_10") (pin "C") (pinfunction "C_C") (pintype "passive"))
      (node (ref "L5_10") (pin "C") (pinfunction "C_C") (pintype "passive"))
      (node (ref "L6_10") (pin "C") (pinfunction "C_C") (pintype "passive"))
      (node (ref "L7_10") (pin "C") (pinfunction "C_C") (pintype "passive"))
      (node (ref "L8_10") (pin "C") (pinfunction "C_C") (pintype "passive"))
      (node (ref "L9_10") (pin "C") (pinfunction "C_C") (pintype "passive"))
      (node (ref "R10") (pin "2") (pinfunction "2_2") (pintype "passive"))
    )
    (net (code "25") (name "/DR11") (class "Default")
      (node (ref "L10_11") (pin "C") (pinfunction "C_C") (pintype "passive"))
      (node (ref "L11_1") (pin "A") (pinfunction "A_A") (pintype "passive"))
      (node (ref "L11_10") (pin "A") (pinfunction "A_A") (pintype "passive"))
      (node (ref "L11_12") (pin "A") (pinfunction "A_A") (pintype "passive"))
      (node (ref "L11_2") (pin "A") (pinfunction "A_A") (pintype "passive"))
      (node (ref "L11_3") (pin "A") (pinfunction "A_A") (pintype "passive"))
      (node (ref "L11_4") (pin "A") (pinfunction "A_A") (pintype "passive"))
      (node (ref "L11_5") (pin "A") (pinfunction "A_A") (pintype "passive"))
      (node (ref "L11_6") (pin "A") (pinfunction "A_A") (pintype "passive"))
      (node (ref "L11_7") (pin "A") (pinfunction "A_A") (pintype "passive"))
      (node (ref "L11_8") (pin "A") (pinfunction "A_A") (pintype "passive"))
      (node (ref "L11_9") (pin "A") (pinfunction "A_A") (pintype "passive"))
      (node (ref "L12_11") (pin "C") (pinfunction "C_C") (pintype "passive"))
      (node (ref "L1_11") (pin "C") (pinfunction "C_C") (pintype "passive"))
      (node (ref "L2_11") (pin "C") (pinfunction "C_C") (pintype "passive"))
      (node (ref "L3_11") (pin "C") (pinfunction "C_C") (pintype "passive"))
      (node (ref "L4_11") (pin "C") (pinfunction "C_C") (pintype "passive"))
      (node (ref "L5_11") (pin "C") (pinfunction "C_C") (pintype "passive"))
      (node (ref "L6_11") (pin "C") (pinfunction "C_C") (pintype "passive"))
      (node (ref "L7_11") (pin "C") (pinfunction "C_C") (pintype "passive"))
      (node (ref "L8_11") (pin "C") (pinfunction "C_C") (pintype "passive"))
      (node (ref "L9_11") (pin "C") (pinfunction "C_C") (pintype "passive"))
      (node (ref "R11") (pin "2") (pinfunction "2_2") (pintype "passive"))
    )
    (net (code "26") (name "/DR12") (class "Default")
      (node (ref "L10_12") (pin "C") (pinfunction "C_C") (pintype "passive"))
      (node (ref "L11_12") (pin "C") (pinfunction "C_C") (pintype "passive"))
      (node (ref "L12_1") (pin "A") (pinfunction "A_A") (pintype "passive"))
      (node (ref "L12_10") (pin "A") (pinfunction "A_A") (pintype "passive"))
      (node (ref "L12_11") (pin "A") (pinfunction "A_A") (pintype "passive"))
      (node (ref "L12_2") (pin "A") (pinfunction "A_A") (pintype "passive"))
      (node (ref "L12_3") (pin "A") (pinfunction "A_A") (pintype "passive"))
      (node (ref "L12_4") (pin "A") (pinfunction "A_A") (pintype "passive"))
      (node (ref "L12_5") (pin "A") (pinfunction "A_A") (pintype "passive"))
      (node (ref "L12_6") (pin "A") (pinfunction "A_A") (pintype "passive"))
      (node (ref "L12_7") (pin "A") (pinfunction "A_A") (pintype "passive"))
      (node (ref "L12_8") (pin "A") (pinfunction "A_A") (pintype "passive"))
      (node (ref "L12_9") (pin "A") (pinfunction "A_A") (pintype "passive"))
      (node (ref "L1_12") (pin "C") (pinfunction "C_C") (pintype "passive"))
      (node (ref "L2_12") (pin "C") (pinfunction "C_C") (pintype "passive"))
      (node (ref "L3_12") (pin "C") (pinfunction "C_C") (pintype "passive"))
      (node (ref "L4_12") (pin "C") (pinfunction "C_C") (pintype "passive"))
      (node (ref "L5_12") (pin "C") (pinfunction "C_C") (pintype "passive"))
      (node (ref "L6_12") (pin "C") (pinfunction "C_C") (pintype "passive"))
      (node (ref "L7_12") (pin "C") (pinfunction "C_C") (pintype "passive"))
      (node (ref "L8_12") (pin "C") (pinfunction "C_C") (pintype "passive"))
      (node (ref "L9_12") (pin "C") (pinfunction "C_C") (pintype "passive"))
      (node (ref "R12") (pin "2") (pinfunction "2_2") (pintype "passive"))
    )
    (net (code "27") (name "/MISO") (class "Default")
      (node (ref "IC1") (pin "16") (pinfunction "PB4(MISO)_16") (pintype "bidirectional"))
      (node (ref "J1") (pin "P$1") (pinfunction "1_P$1") (pintype "passive"))
    )
    (net (code "28") (name "/MOSI") (class "Default")
      (node (ref "IC1") (pin "15") (pinfunction "PB3(MOSI/OC2)_15") (pintype "bidirectional"))
      (node (ref "J1") (pin "P$4") (pinfunction "4_P$4") (pintype "passive"))
    )
    (net (code "29") (name "/RESET") (class "Default")
      (node (ref "IC1") (pin "29") (pinfunction "PC6(/RESET)_29") (pintype "bidirectional"))
      (node (ref "J1") (pin "P$5") (pinfunction "5_P$5") (pintype "passive"))
    )
    (net (code "30") (name "/SCK") (class "Default")
      (node (ref "IC1") (pin "17") (pinfunction "PB5(SCK)_17") (pintype "bidirectional"))
      (node (ref "J1") (pin "P$3") (pinfunction "3_P$3") (pintype "passive"))
    )
    (net (code "31") (name "GNDA") (class "Default")
      (node (ref "C1") (pin "2") (pinfunction "2_2") (pintype "passive"))
      (node (ref "C2") (pin "2") (pinfunction "2_2") (pintype "passive"))
      (node (ref "C3") (pin "2") (pinfunction "2_2") (pintype "passive"))
      (node (ref "C4") (pin "2") (pinfunction "2_2") (pintype "passive"))
      (node (ref "DOWNSW") (pin "B2") (pinfunction "2_B2") (pintype "passive"))
      (node (ref "GND") (pin "TP") (pinfunction "TP_TP") (pintype "input"))
      (node (ref "IC1") (pin "21") (pinfunction "GND_21") (pintype "power_in"))
      (node (ref "IC1") (pin "3") (pinfunction "GND_3") (pintype "power_in"))
      (node (ref "IC1") (pin "5") (pinfunction "GND_5") (pintype "power_in"))
      (node (ref "J1") (pin "P$7") (pinfunction "6_P$7") (pintype "passive"))
      (node (ref "R13") (pin "1") (pinfunction "1_1") (pintype "passive"))
      (node (ref "UPSW") (pin "B2") (pinfunction "2_B2") (pintype "passive"))
    )
    (net (code "32") (name "Net-(DOWNSW-1)") (class "Default")
      (node (ref "DOWNSW") (pin "A2") (pinfunction "1_A2") (pintype "passive"))
      (node (ref "IC1") (pin "13") (pinfunction "PB1(OC1A)_13") (pintype "bidirectional"))
    )
    (net (code "33") (name "Net-(IC1-PB2(SS{slash}OC1B))") (class "Default")
      (node (ref "IC1") (pin "14") (pinfunction "PB2(SS/OC1B)_14") (pintype "bidirectional"))
      (node (ref "UPSW") (pin "A2") (pinfunction "1_A2") (pintype "passive"))
    )
    (net (code "34") (name "Net-(IC1-PB6(XTAL1{slash}TOSC1))") (class "Default")
      (node (ref "C1") (pin "1") (pinfunction "1_1") (pintype "passive"))
      (node (ref "IC1") (pin "7") (pinfunction "PB6(XTAL1/TOSC1)_7") (pintype "bidirectional"))
      (node (ref "Q1") (pin "1") (pinfunction "1_1") (pintype "passive"))
    )
    (net (code "35") (name "Net-(IC1-PB7(XTAL2{slash}TOSC2))") (class "Default")
      (node (ref "C2") (pin "1") (pinfunction "1_1") (pintype "passive"))
      (node (ref "IC1") (pin "8") (pinfunction "PB7(XTAL2/TOSC2)_8") (pintype "bidirectional"))
      (node (ref "Q1") (pin "3") (pinfunction "3_3") (pintype "passive"))
    )
    (net (code "36") (name "Net-(IC2-ADJ)") (class "Default")
      (node (ref "IC2") (pin "1") (pinfunction "ADJ_1") (pintype "input"))
      (node (ref "R13") (pin "2") (pinfunction "2_2") (pintype "passive"))
      (node (ref "R14") (pin "1") (pinfunction "1_1") (pintype "passive"))
    )
    (net (code "37") (name "unconnected-(IC1-ADC6-Pad19)") (class "Default")
      (node (ref "IC1") (pin "19") (pinfunction "ADC6_19") (pintype "bidirectional"))
    )
    (net (code "38") (name "unconnected-(IC1-ADC7-Pad22)") (class "Default")
      (node (ref "IC1") (pin "22") (pinfunction "ADC7_22") (pintype "bidirectional"))
    )
    (net (code "39") (name "unconnected-(IC1-PB0(ICP)-Pad12)") (class "Default")
      (node (ref "IC1") (pin "12") (pinfunction "PB0(ICP)_12") (pintype "bidirectional"))
    )
    (net (code "40") (name "unconnected-(IC1-PC4(ADC4{slash}SDA)-Pad27)") (class "Default")
      (node (ref "IC1") (pin "27") (pinfunction "PC4(ADC4/SDA)_27") (pintype "bidirectional"))
    )
    (net (code "41") (name "unconnected-(IC1-PC5(ADC5{slash}SCL)-Pad28)") (class "Default")
      (node (ref "IC1") (pin "28") (pinfunction "PC5(ADC5/SCL)_28") (pintype "bidirectional"))
    )
    (net (code "42") (name "unconnected-(Q1-Pad2)") (class "Default")
      (node (ref "Q1") (pin "2") (pinfunction "2_2") (pintype "passive"))
    )
    (net (code "43") (name "unconnected-(Q1-Pad4)") (class "Default")
      (node (ref "Q1") (pin "4") (pinfunction "4_4") (pintype "passive"))
    )
  )
)
